# usbasp.net
KiCad netlist of a schematic drawn in EAGLE
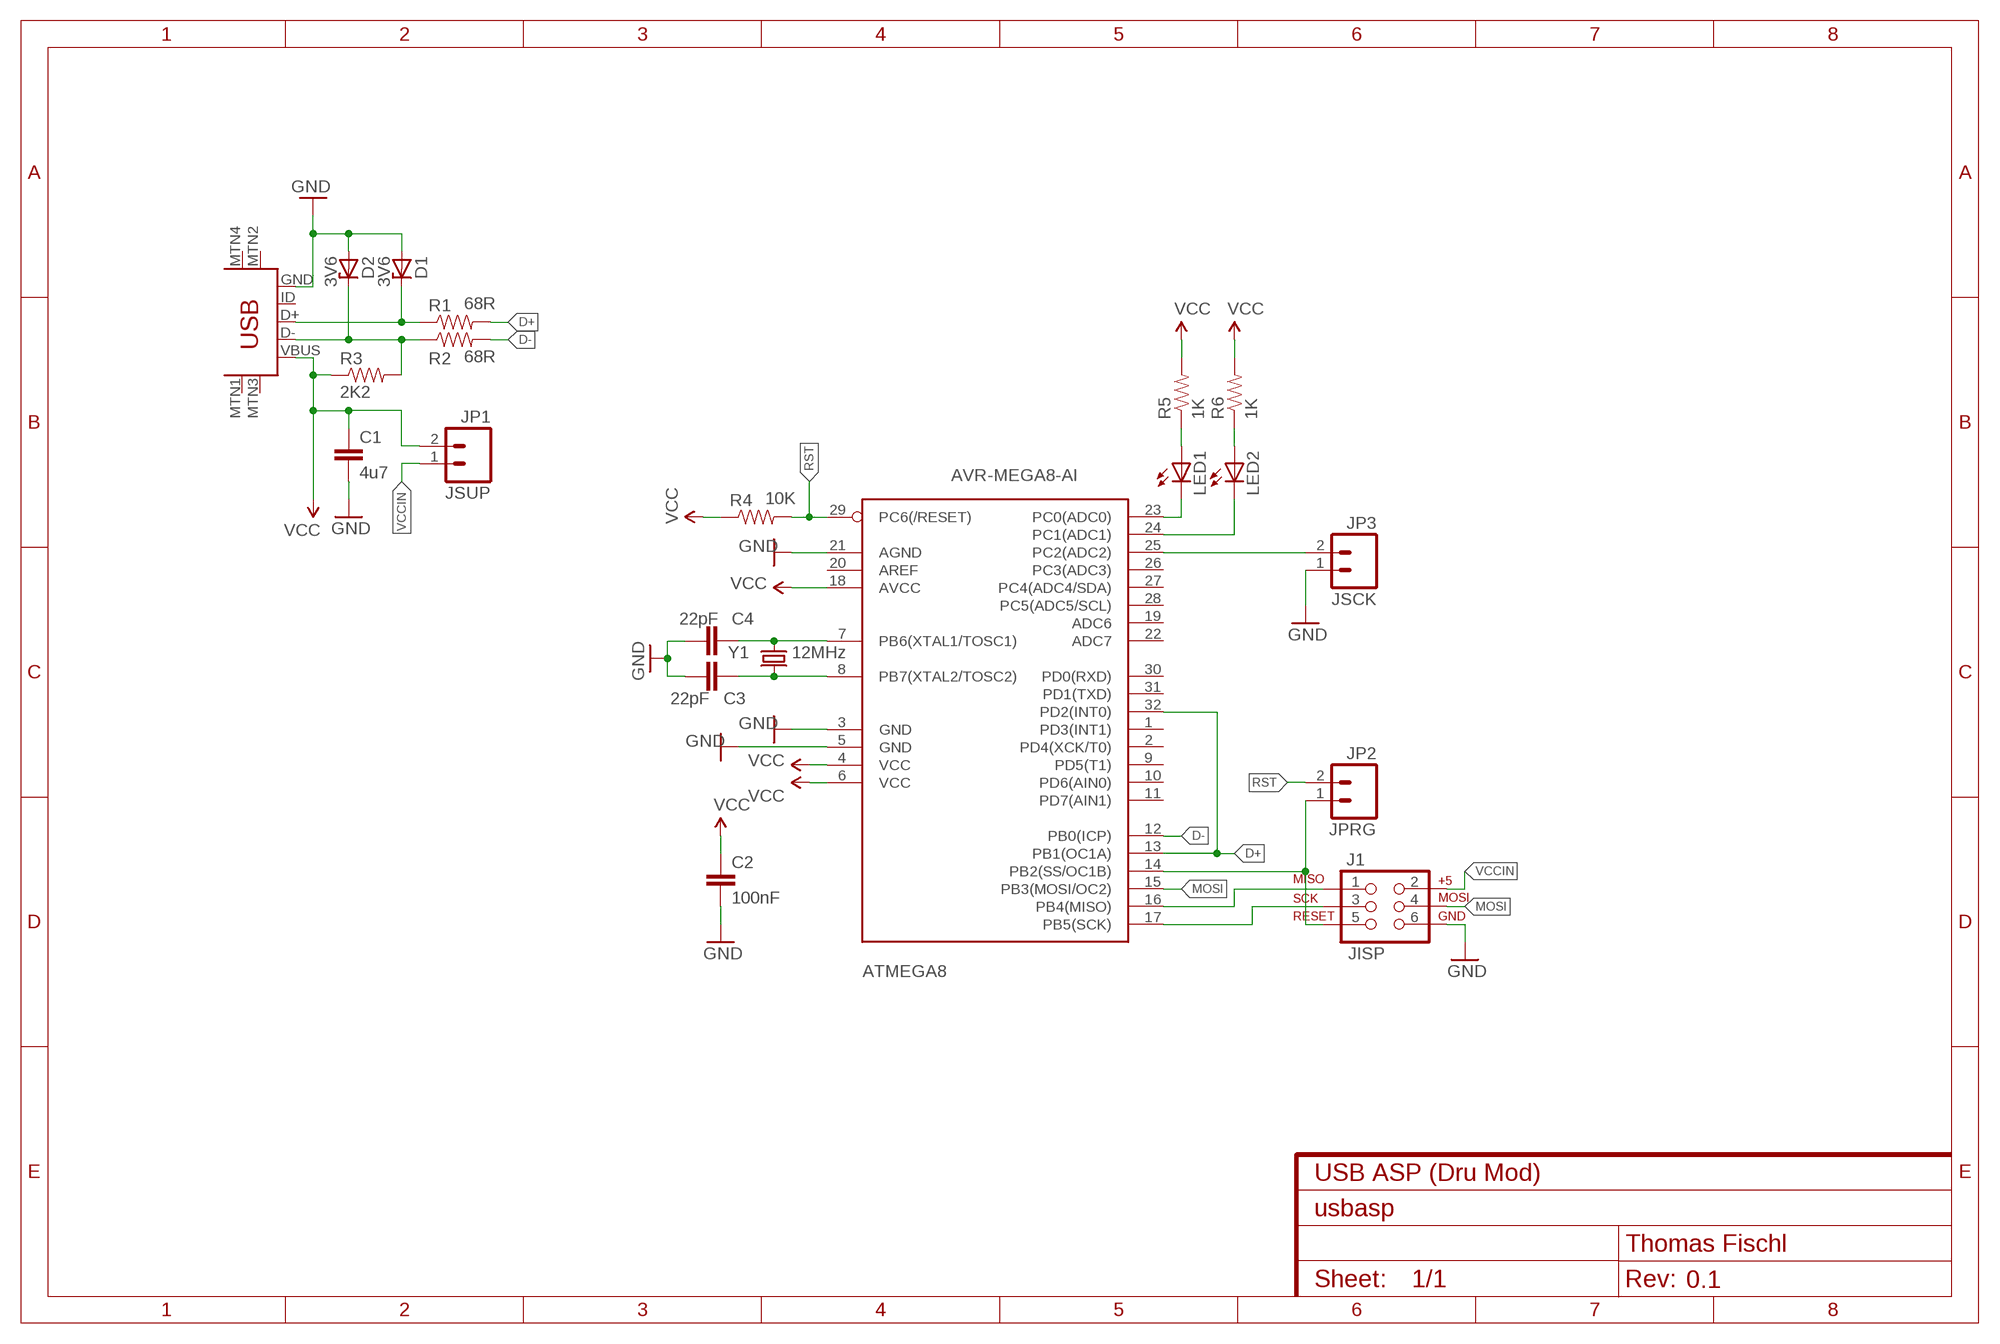
[diagram p0: schematic, sheet 1]

(export (version "E")
  (design (tool "Eeschema 10.0.6"))
  (components
    (comp (ref "ATMEGA8")
      (value "AVR-MEGA8-AI")
      (footprint "eagle-import:TQFP32-08")
      (libsource (lib "eagle-import") (part "AVR-MEGA8-AI"))
    )
    (comp (ref "C1")
      (value "4u7")
      (footprint "eagle-import:0603-CAP")
      (libsource (lib "eagle-import") (part "CAP0603-CAP"))
    )
    (comp (ref "C2")
      (value "100nF")
      (footprint "eagle-import:0805")
      (libsource (lib "eagle-import") (part "CAP0805"))
    )
    (comp (ref "C3")
      (value "22pF")
      (footprint "eagle-import:0805")
      (libsource (lib "eagle-import") (part "CAP0805"))
    )
    (comp (ref "C4")
      (value "22pF")
      (footprint "eagle-import:0805")
      (libsource (lib "eagle-import") (part "CAP0805"))
    )
    (comp (ref "D1")
      (value "3V6")
      (footprint "eagle-import:SOD80C")
      (libsource (lib "eagle-import") (part "ZENER-DIODESOD80C"))
    )
    (comp (ref "D2")
      (value "3V6")
      (footprint "eagle-import:SOD80C")
      (libsource (lib "eagle-import") (part "ZENER-DIODESOD80C"))
    )
    (comp (ref "J1")
      (value "JISP")
      (footprint "eagle-import:2X3")
      (libsource (lib "eagle-import") (part "AVR_SPI_PRG_6PTH"))
    )
    (comp (ref "JP1")
      (value "JSUP")
      (footprint "eagle-import:1X02")
      (libsource (lib "eagle-import") (part "M02PTH"))
    )
    (comp (ref "JP2")
      (value "JPRG")
      (footprint "eagle-import:1X02")
      (libsource (lib "eagle-import") (part "M02PTH"))
    )
    (comp (ref "JP3")
      (value "JSCK")
      (footprint "eagle-import:1X02")
      (libsource (lib "eagle-import") (part "M02PTH"))
    )
    (comp (ref "LED1")
      (value "LEDCHIPLED_0805")
      (footprint "eagle-import:CHIPLED_0805")
      (libsource (lib "eagle-import") (part "LEDCHIPLED_0805"))
    )
    (comp (ref "LED2")
      (value "LEDCHIPLED_0805")
      (footprint "eagle-import:CHIPLED_0805")
      (libsource (lib "eagle-import") (part "LEDCHIPLED_0805"))
    )
    (comp (ref "R1")
      (value "68R")
      (footprint "eagle-import:0603-RES")
      (libsource (lib "eagle-import") (part "RESISTOR0603-RES"))
    )
    (comp (ref "R2")
      (value "68R")
      (footprint "eagle-import:0603-RES")
      (libsource (lib "eagle-import") (part "RESISTOR0603-RES"))
    )
    (comp (ref "R3")
      (value "2K2")
      (footprint "eagle-import:0603-RES")
      (libsource (lib "eagle-import") (part "RESISTOR0603-RES"))
    )
    (comp (ref "R4")
      (value "10K")
      (footprint "eagle-import:0603-RES")
      (libsource (lib "eagle-import") (part "RESISTOR0603-RES"))
    )
    (comp (ref "R5")
      (value "1K")
      (footprint "eagle-import:0603-RES")
      (libsource (lib "eagle-import") (part "RESISTOR0603-RES"))
    )
    (comp (ref "R6")
      (value "1K")
      (footprint "eagle-import:0603-RES")
      (libsource (lib "eagle-import") (part "RESISTOR0603-RES"))
    )
    (comp (ref "U$2")
      (value "USB-MINIB-5PIN")
      (footprint "eagle-import:USB-MINIB")
      (libsource (lib "eagle-import") (part "USB-MINIB-5PIN"))
    )
    (comp (ref "Y1")
      (value "12MHz")
      (footprint "eagle-import:HC49UP")
      (libsource (lib "eagle-import") (part "CRYSTALSMD"))
    )
  )
  (nets
    (net (code "1") (name "D+") (class "Default")
      (node (ref "ATMEGA8") (pin "13") (pinfunction "PB1(OC1A)_13") (pintype "bidirectional"))
      (node (ref "ATMEGA8") (pin "32") (pinfunction "PD2(INT0)_32") (pintype "bidirectional"))
      (node (ref "R1") (pin "2") (pinfunction "2_2") (pintype "passive"))
    )
    (net (code "2") (name "D-") (class "Default")
      (node (ref "ATMEGA8") (pin "12") (pinfunction "PB0(ICP)_12") (pintype "bidirectional"))
      (node (ref "R2") (pin "2") (pinfunction "2_2") (pintype "passive"))
    )
    (net (code "3") (name "GND") (class "Default")
      (node (ref "ATMEGA8") (pin "21") (pinfunction "AGND_21") (pintype "bidirectional"))
      (node (ref "ATMEGA8") (pin "3") (pinfunction "GND_3") (pintype "bidirectional"))
      (node (ref "ATMEGA8") (pin "5") (pinfunction "GND_5") (pintype "bidirectional"))
      (node (ref "C1") (pin "2") (pinfunction "2_2") (pintype "passive"))
      (node (ref "C2") (pin "2") (pinfunction "2_2") (pintype "passive"))
      (node (ref "C3") (pin "2") (pinfunction "2_2") (pintype "passive"))
      (node (ref "C4") (pin "1") (pinfunction "1_1") (pintype "passive"))
      (node (ref "D1") (pin "A") (pinfunction "A_A") (pintype "passive"))
      (node (ref "D2") (pin "A") (pinfunction "A_A") (pintype "passive"))
      (node (ref "J1") (pin "6") (pinfunction "6_6") (pintype "passive"))
      (node (ref "JP3") (pin "1") (pinfunction "1_1") (pintype "passive"))
      (node (ref "U$2") (pin "GND") (pinfunction "GND_GND") (pintype "bidirectional"))
    )
    (net (code "4") (name "MOSI") (class "Default")
      (node (ref "ATMEGA8") (pin "15") (pinfunction "PB3(MOSI/OC2)_15") (pintype "bidirectional"))
      (node (ref "J1") (pin "4") (pinfunction "4_4") (pintype "passive"))
    )
    (net (code "5") (name "Net-(ATMEGA8-PB2(SS{slash}OC1B))") (class "Default")
      (node (ref "ATMEGA8") (pin "14") (pinfunction "PB2(SS/OC1B)_14") (pintype "bidirectional"))
      (node (ref "J1") (pin "5") (pinfunction "5_5") (pintype "passive"))
      (node (ref "JP2") (pin "1") (pinfunction "1_1") (pintype "passive"))
    )
    (net (code "6") (name "Net-(ATMEGA8-PB4(MISO))") (class "Default")
      (node (ref "ATMEGA8") (pin "16") (pinfunction "PB4(MISO)_16") (pintype "bidirectional"))
      (node (ref "J1") (pin "1") (pinfunction "1_1") (pintype "passive"))
    )
    (net (code "7") (name "Net-(ATMEGA8-PB5(SCK))") (class "Default")
      (node (ref "ATMEGA8") (pin "17") (pinfunction "PB5(SCK)_17") (pintype "bidirectional"))
      (node (ref "J1") (pin "3") (pinfunction "3_3") (pintype "passive"))
    )
    (net (code "8") (name "Net-(ATMEGA8-PB6(XTAL1{slash}TOSC1))") (class "Default")
      (node (ref "ATMEGA8") (pin "7") (pinfunction "PB6(XTAL1/TOSC1)_7") (pintype "bidirectional"))
      (node (ref "C4") (pin "2") (pinfunction "2_2") (pintype "passive"))
      (node (ref "Y1") (pin "1") (pinfunction "1_1") (pintype "passive"))
    )
    (net (code "9") (name "Net-(ATMEGA8-PB7(XTAL2{slash}TOSC2))") (class "Default")
      (node (ref "ATMEGA8") (pin "8") (pinfunction "PB7(XTAL2/TOSC2)_8") (pintype "bidirectional"))
      (node (ref "C3") (pin "1") (pinfunction "1_1") (pintype "passive"))
      (node (ref "Y1") (pin "2") (pinfunction "2_2") (pintype "passive"))
    )
    (net (code "10") (name "Net-(ATMEGA8-PC0(ADC0))") (class "Default")
      (node (ref "ATMEGA8") (pin "23") (pinfunction "PC0(ADC0)_23") (pintype "bidirectional"))
      (node (ref "LED1") (pin "C") (pinfunction "C_C") (pintype "passive"))
    )
    (net (code "11") (name "Net-(ATMEGA8-PC1(ADC1))") (class "Default")
      (node (ref "ATMEGA8") (pin "24") (pinfunction "PC1(ADC1)_24") (pintype "bidirectional"))
      (node (ref "LED2") (pin "C") (pinfunction "C_C") (pintype "passive"))
    )
    (net (code "12") (name "Net-(ATMEGA8-PC2(ADC2))") (class "Default")
      (node (ref "ATMEGA8") (pin "25") (pinfunction "PC2(ADC2)_25") (pintype "bidirectional"))
      (node (ref "JP3") (pin "2") (pinfunction "2_2") (pintype "passive"))
    )
    (net (code "13") (name "Net-(D1-PadC)") (class "Default")
      (node (ref "D1") (pin "C") (pinfunction "C_C") (pintype "passive"))
      (node (ref "R1") (pin "1") (pinfunction "1_1") (pintype "passive"))
      (node (ref "U$2") (pin "D+") (pinfunction "D+_D+") (pintype "bidirectional"))
    )
    (net (code "14") (name "Net-(D2-PadC)") (class "Default")
      (node (ref "D2") (pin "C") (pinfunction "C_C") (pintype "passive"))
      (node (ref "R2") (pin "1") (pinfunction "1_1") (pintype "passive"))
      (node (ref "R3") (pin "2") (pinfunction "2_2") (pintype "passive"))
      (node (ref "U$2") (pin "D-") (pinfunction "D-_D-") (pintype "bidirectional"))
    )
    (net (code "15") (name "Net-(LED1-PadA)") (class "Default")
      (node (ref "LED1") (pin "A") (pinfunction "A_A") (pintype "passive"))
      (node (ref "R5") (pin "1") (pinfunction "1_1") (pintype "passive"))
    )
    (net (code "16") (name "Net-(LED2-PadA)") (class "Default")
      (node (ref "LED2") (pin "A") (pinfunction "A_A") (pintype "passive"))
      (node (ref "R6") (pin "1") (pinfunction "1_1") (pintype "passive"))
    )
    (net (code "17") (name "RST") (class "Default")
      (node (ref "ATMEGA8") (pin "29") (pinfunction "PC6(/RESET)_29") (pintype "bidirectional"))
      (node (ref "JP2") (pin "2") (pinfunction "2_2") (pintype "passive"))
      (node (ref "R4") (pin "2") (pinfunction "2_2") (pintype "passive"))
    )
    (net (code "18") (name "VCC") (class "Default")
      (node (ref "ATMEGA8") (pin "18") (pinfunction "AVCC_18") (pintype "bidirectional"))
      (node (ref "ATMEGA8") (pin "4") (pinfunction "VCC_4") (pintype "bidirectional"))
      (node (ref "ATMEGA8") (pin "6") (pinfunction "VCC_6") (pintype "bidirectional"))
      (node (ref "C1") (pin "1") (pinfunction "1_1") (pintype "passive"))
      (node (ref "C2") (pin "1") (pinfunction "1_1") (pintype "passive"))
      (node (ref "JP1") (pin "2") (pinfunction "2_2") (pintype "passive"))
      (node (ref "R3") (pin "1") (pinfunction "1_1") (pintype "passive"))
      (node (ref "R4") (pin "1") (pinfunction "1_1") (pintype "passive"))
      (node (ref "R5") (pin "2") (pinfunction "2_2") (pintype "passive"))
      (node (ref "R6") (pin "2") (pinfunction "2_2") (pintype "passive"))
      (node (ref "U$2") (pin "VBUS") (pinfunction "VBUS_VBUS") (pintype "bidirectional"))
    )
    (net (code "19") (name "VCCIN") (class "Default")
      (node (ref "J1") (pin "2") (pinfunction "2_2") (pintype "passive"))
      (node (ref "JP1") (pin "1") (pinfunction "1_1") (pintype "passive"))
    )
    (net (code "20") (name "unconnected-(ATMEGA8-ADC6-Pad19)") (class "Default")
      (node (ref "ATMEGA8") (pin "19") (pinfunction "ADC6_19") (pintype "bidirectional"))
    )
    (net (code "21") (name "unconnected-(ATMEGA8-ADC7-Pad22)") (class "Default")
      (node (ref "ATMEGA8") (pin "22") (pinfunction "ADC7_22") (pintype "bidirectional"))
    )
    (net (code "22") (name "unconnected-(ATMEGA8-AREF-Pad20)") (class "Default")
      (node (ref "ATMEGA8") (pin "20") (pinfunction "AREF_20") (pintype "bidirectional"))
    )
    (net (code "23") (name "unconnected-(ATMEGA8-PC3(ADC3)-Pad26)") (class "Default")
      (node (ref "ATMEGA8") (pin "26") (pinfunction "PC3(ADC3)_26") (pintype "bidirectional"))
    )
    (net (code "24") (name "unconnected-(ATMEGA8-PC4(ADC4{slash}SDA)-Pad27)") (class "Default")
      (node (ref "ATMEGA8") (pin "27") (pinfunction "PC4(ADC4/SDA)_27") (pintype "bidirectional"))
    )
    (net (code "25") (name "unconnected-(ATMEGA8-PC5(ADC5{slash}SCL)-Pad28)") (class "Default")
      (node (ref "ATMEGA8") (pin "28") (pinfunction "PC5(ADC5/SCL)_28") (pintype "bidirectional"))
    )
    (net (code "26") (name "unconnected-(ATMEGA8-PD0(RXD)-Pad30)") (class "Default")
      (node (ref "ATMEGA8") (pin "30") (pinfunction "PD0(RXD)_30") (pintype "bidirectional"))
    )
    (net (code "27") (name "unconnected-(ATMEGA8-PD1(TXD)-Pad31)") (class "Default")
      (node (ref "ATMEGA8") (pin "31") (pinfunction "PD1(TXD)_31") (pintype "bidirectional"))
    )
    (net (code "28") (name "unconnected-(ATMEGA8-PD3(INT1)-Pad1)") (class "Default")
      (node (ref "ATMEGA8") (pin "1") (pinfunction "PD3(INT1)_1") (pintype "bidirectional"))
    )
    (net (code "29") (name "unconnected-(ATMEGA8-PD4(XCK{slash}T0)-Pad2)") (class "Default")
      (node (ref "ATMEGA8") (pin "2") (pinfunction "PD4(XCK/T0)_2") (pintype "bidirectional"))
    )
    (net (code "30") (name "unconnected-(ATMEGA8-PD5(T1)-Pad9)") (class "Default")
      (node (ref "ATMEGA8") (pin "9") (pinfunction "PD5(T1)_9") (pintype "bidirectional"))
    )
    (net (code "31") (name "unconnected-(ATMEGA8-PD6(AIN0)-Pad10)") (class "Default")
      (node (ref "ATMEGA8") (pin "10") (pinfunction "PD6(AIN0)_10") (pintype "bidirectional"))
    )
    (net (code "32") (name "unconnected-(ATMEGA8-PD7(AIN1)-Pad11)") (class "Default")
      (node (ref "ATMEGA8") (pin "11") (pinfunction "PD7(AIN1)_11") (pintype "bidirectional"))
    )
    (net (code "33") (name "unconnected-(U$2-MTN1-PadMTN3)") (class "Default")
      (node (ref "U$2") (pin "MTN3") (pinfunction "MTN1_MTN3") (pintype "bidirectional"))
    )
    (net (code "34") (name "unconnected-(U$2-MTN2-PadMTN1)") (class "Default")
      (node (ref "U$2") (pin "MTN1") (pinfunction "MTN2_MTN1") (pintype "bidirectional"))
    )
    (net (code "35") (name "unconnected-(U$2-MTN3-PadMTN2)") (class "Default")
      (node (ref "U$2") (pin "MTN2") (pinfunction "MTN3_MTN2") (pintype "bidirectional"))
    )
    (net (code "36") (name "unconnected-(U$2-PadID)") (class "Default")
      (node (ref "U$2") (pin "ID") (pinfunction "ID_ID") (pintype "bidirectional"))
    )
    (net (code "37") (name "unconnected-(U$2-PadMTN4)") (class "Default")
      (node (ref "U$2") (pin "MTN4") (pinfunction "MTN4_MTN4") (pintype "bidirectional"))
    )
  )
)
